# Spartan3_TestBoard_2.net
KiCad netlist of a schematic drawn in Altium Designer
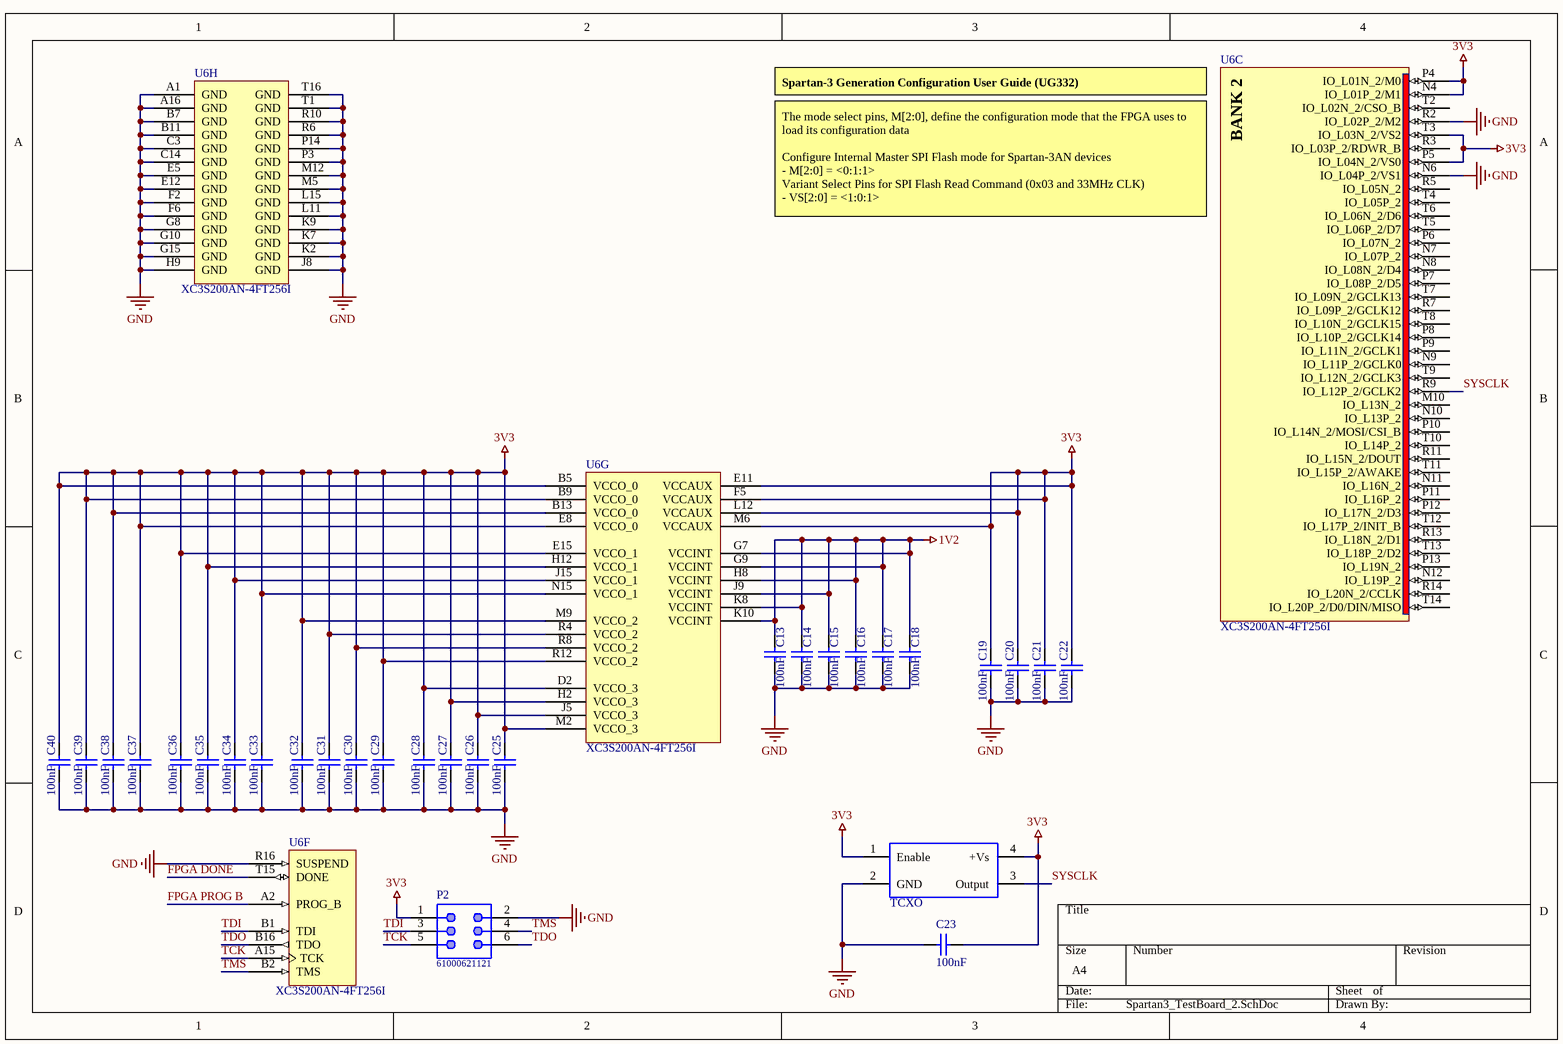
[diagram p0: Spartan3_TestBoard_2.SchDoc]

(export (version "E")
  (design (tool "Eeschema 10.0.6"))
  (components
    (comp (ref "C13")
      (value "100nF")
      (footprint "WCAP-CSGP_0402")
      (description "WCAP-CSGP General Purpose Ceramic Capacitors, size 0402, 100nF, +/-10%, 10VDC")
      (fields (field (name "PART NUMBER") "885012205018") (field (name "PUBLISHER") "Wurth Elektronik"))
      (libsource (lib "Altium_WCAP-CSGP (rev19a)") (part "885012205018"))
    )
    (comp (ref "C14")
      (value "100nF")
      (footprint "WCAP-CSGP_0402")
      (description "WCAP-CSGP General Purpose Ceramic Capacitors, size 0402, 100nF, +/-10%, 10VDC")
      (fields (field (name "PART NUMBER") "885012205018") (field (name "PUBLISHER") "Wurth Elektronik"))
      (libsource (lib "Altium_WCAP-CSGP (rev19a)") (part "885012205018"))
    )
    (comp (ref "C15")
      (value "100nF")
      (footprint "WCAP-CSGP_0402")
      (description "WCAP-CSGP General Purpose Ceramic Capacitors, size 0402, 100nF, +/-10%, 10VDC")
      (fields (field (name "PART NUMBER") "885012205018") (field (name "PUBLISHER") "Wurth Elektronik"))
      (libsource (lib "Altium_WCAP-CSGP (rev19a)") (part "885012205018"))
    )
    (comp (ref "C16")
      (value "100nF")
      (footprint "WCAP-CSGP_0402")
      (description "WCAP-CSGP General Purpose Ceramic Capacitors, size 0402, 100nF, +/-10%, 10VDC")
      (fields (field (name "PART NUMBER") "885012205018") (field (name "PUBLISHER") "Wurth Elektronik"))
      (libsource (lib "Altium_WCAP-CSGP (rev19a)") (part "885012205018"))
    )
    (comp (ref "C17")
      (value "100nF")
      (footprint "WCAP-CSGP_0402")
      (description "WCAP-CSGP General Purpose Ceramic Capacitors, size 0402, 100nF, +/-10%, 10VDC")
      (fields (field (name "PART NUMBER") "885012205018") (field (name "PUBLISHER") "Wurth Elektronik"))
      (libsource (lib "Altium_WCAP-CSGP (rev19a)") (part "885012205018"))
    )
    (comp (ref "C18")
      (value "100nF")
      (footprint "WCAP-CSGP_0402")
      (description "WCAP-CSGP General Purpose Ceramic Capacitors, size 0402, 100nF, +/-10%, 10VDC")
      (fields (field (name "PART NUMBER") "885012205018") (field (name "PUBLISHER") "Wurth Elektronik"))
      (libsource (lib "Altium_WCAP-CSGP (rev19a)") (part "885012205018"))
    )
    (comp (ref "C19")
      (value "100nF")
      (footprint "WCAP-CSGP_0402")
      (description "WCAP-CSGP General Purpose Ceramic Capacitors, size 0402, 100nF, +/-10%, 10VDC")
      (fields (field (name "PART NUMBER") "885012205018") (field (name "PUBLISHER") "Wurth Elektronik"))
      (libsource (lib "Altium_WCAP-CSGP (rev19a)") (part "885012205018"))
    )
    (comp (ref "C20")
      (value "100nF")
      (footprint "WCAP-CSGP_0402")
      (description "WCAP-CSGP General Purpose Ceramic Capacitors, size 0402, 100nF, +/-10%, 10VDC")
      (fields (field (name "PART NUMBER") "885012205018") (field (name "PUBLISHER") "Wurth Elektronik"))
      (libsource (lib "Altium_WCAP-CSGP (rev19a)") (part "885012205018"))
    )
    (comp (ref "C21")
      (value "100nF")
      (footprint "WCAP-CSGP_0402")
      (description "WCAP-CSGP General Purpose Ceramic Capacitors, size 0402, 100nF, +/-10%, 10VDC")
      (fields (field (name "PART NUMBER") "885012205018") (field (name "PUBLISHER") "Wurth Elektronik"))
      (libsource (lib "Altium_WCAP-CSGP (rev19a)") (part "885012205018"))
    )
    (comp (ref "C22")
      (value "100nF")
      (footprint "WCAP-CSGP_0402")
      (description "WCAP-CSGP General Purpose Ceramic Capacitors, size 0402, 100nF, +/-10%, 10VDC")
      (fields (field (name "PART NUMBER") "885012205018") (field (name "PUBLISHER") "Wurth Elektronik"))
      (libsource (lib "Altium_WCAP-CSGP (rev19a)") (part "885012205018"))
    )
    (comp (ref "C23")
      (value "100nF")
      (footprint "WCAP-CSGP_0402")
      (description "WCAP-CSGP General Purpose Ceramic Capacitors, size 0402, 100nF, +/-10%, 10VDC")
      (fields (field (name "PART NUMBER") "885012205018") (field (name "PUBLISHER") "Wurth Elektronik"))
      (libsource (lib "Altium_WCAP-CSGP (rev19a)") (part "885012205018"))
    )
    (comp (ref "C25")
      (value "100nF")
      (footprint "WCAP-CSGP_0402")
      (description "WCAP-CSGP General Purpose Ceramic Capacitors, size 0402, 100nF, +/-10%, 10VDC")
      (fields (field (name "PART NUMBER") "885012205018") (field (name "PUBLISHER") "Wurth Elektronik"))
      (libsource (lib "Altium_WCAP-CSGP (rev19a)") (part "885012205018"))
    )
    (comp (ref "C26")
      (value "100nF")
      (footprint "WCAP-CSGP_0402")
      (description "WCAP-CSGP General Purpose Ceramic Capacitors, size 0402, 100nF, +/-10%, 10VDC")
      (fields (field (name "PART NUMBER") "885012205018") (field (name "PUBLISHER") "Wurth Elektronik"))
      (libsource (lib "Altium_WCAP-CSGP (rev19a)") (part "885012205018"))
    )
    (comp (ref "C27")
      (value "100nF")
      (footprint "WCAP-CSGP_0402")
      (description "WCAP-CSGP General Purpose Ceramic Capacitors, size 0402, 100nF, +/-10%, 10VDC")
      (fields (field (name "PART NUMBER") "885012205018") (field (name "PUBLISHER") "Wurth Elektronik"))
      (libsource (lib "Altium_WCAP-CSGP (rev19a)") (part "885012205018"))
    )
    (comp (ref "C28")
      (value "100nF")
      (footprint "WCAP-CSGP_0402")
      (description "WCAP-CSGP General Purpose Ceramic Capacitors, size 0402, 100nF, +/-10%, 10VDC")
      (fields (field (name "PART NUMBER") "885012205018") (field (name "PUBLISHER") "Wurth Elektronik"))
      (libsource (lib "Altium_WCAP-CSGP (rev19a)") (part "885012205018"))
    )
    (comp (ref "C29")
      (value "100nF")
      (footprint "WCAP-CSGP_0402")
      (description "WCAP-CSGP General Purpose Ceramic Capacitors, size 0402, 100nF, +/-10%, 10VDC")
      (fields (field (name "PART NUMBER") "885012205018") (field (name "PUBLISHER") "Wurth Elektronik"))
      (libsource (lib "Altium_WCAP-CSGP (rev19a)") (part "885012205018"))
    )
    (comp (ref "C30")
      (value "100nF")
      (footprint "WCAP-CSGP_0402")
      (description "WCAP-CSGP General Purpose Ceramic Capacitors, size 0402, 100nF, +/-10%, 10VDC")
      (fields (field (name "PART NUMBER") "885012205018") (field (name "PUBLISHER") "Wurth Elektronik"))
      (libsource (lib "Altium_WCAP-CSGP (rev19a)") (part "885012205018"))
    )
    (comp (ref "C31")
      (value "100nF")
      (footprint "WCAP-CSGP_0402")
      (description "WCAP-CSGP General Purpose Ceramic Capacitors, size 0402, 100nF, +/-10%, 10VDC")
      (fields (field (name "PART NUMBER") "885012205018") (field (name "PUBLISHER") "Wurth Elektronik"))
      (libsource (lib "Altium_WCAP-CSGP (rev19a)") (part "885012205018"))
    )
    (comp (ref "C32")
      (value "100nF")
      (footprint "WCAP-CSGP_0402")
      (description "WCAP-CSGP General Purpose Ceramic Capacitors, size 0402, 100nF, +/-10%, 10VDC")
      (fields (field (name "PART NUMBER") "885012205018") (field (name "PUBLISHER") "Wurth Elektronik"))
      (libsource (lib "Altium_WCAP-CSGP (rev19a)") (part "885012205018"))
    )
    (comp (ref "C33")
      (value "100nF")
      (footprint "WCAP-CSGP_0402")
      (description "WCAP-CSGP General Purpose Ceramic Capacitors, size 0402, 100nF, +/-10%, 10VDC")
      (fields (field (name "PART NUMBER") "885012205018") (field (name "PUBLISHER") "Wurth Elektronik"))
      (libsource (lib "Altium_WCAP-CSGP (rev19a)") (part "885012205018"))
    )
    (comp (ref "C34")
      (value "100nF")
      (footprint "WCAP-CSGP_0402")
      (description "WCAP-CSGP General Purpose Ceramic Capacitors, size 0402, 100nF, +/-10%, 10VDC")
      (fields (field (name "PART NUMBER") "885012205018") (field (name "PUBLISHER") "Wurth Elektronik"))
      (libsource (lib "Altium_WCAP-CSGP (rev19a)") (part "885012205018"))
    )
    (comp (ref "C35")
      (value "100nF")
      (footprint "WCAP-CSGP_0402")
      (description "WCAP-CSGP General Purpose Ceramic Capacitors, size 0402, 100nF, +/-10%, 10VDC")
      (fields (field (name "PART NUMBER") "885012205018") (field (name "PUBLISHER") "Wurth Elektronik"))
      (libsource (lib "Altium_WCAP-CSGP (rev19a)") (part "885012205018"))
    )
    (comp (ref "C36")
      (value "100nF")
      (footprint "WCAP-CSGP_0402")
      (description "WCAP-CSGP General Purpose Ceramic Capacitors, size 0402, 100nF, +/-10%, 10VDC")
      (fields (field (name "PART NUMBER") "885012205018") (field (name "PUBLISHER") "Wurth Elektronik"))
      (libsource (lib "Altium_WCAP-CSGP (rev19a)") (part "885012205018"))
    )
    (comp (ref "C37")
      (value "100nF")
      (footprint "WCAP-CSGP_0402")
      (description "WCAP-CSGP General Purpose Ceramic Capacitors, size 0402, 100nF, +/-10%, 10VDC")
      (fields (field (name "PART NUMBER") "885012205018") (field (name "PUBLISHER") "Wurth Elektronik"))
      (libsource (lib "Altium_WCAP-CSGP (rev19a)") (part "885012205018"))
    )
    (comp (ref "C38")
      (value "100nF")
      (footprint "WCAP-CSGP_0402")
      (description "WCAP-CSGP General Purpose Ceramic Capacitors, size 0402, 100nF, +/-10%, 10VDC")
      (fields (field (name "PART NUMBER") "885012205018") (field (name "PUBLISHER") "Wurth Elektronik"))
      (libsource (lib "Altium_WCAP-CSGP (rev19a)") (part "885012205018"))
    )
    (comp (ref "C39")
      (value "100nF")
      (footprint "WCAP-CSGP_0402")
      (description "WCAP-CSGP General Purpose Ceramic Capacitors, size 0402, 100nF, +/-10%, 10VDC")
      (fields (field (name "PART NUMBER") "885012205018") (field (name "PUBLISHER") "Wurth Elektronik"))
      (libsource (lib "Altium_WCAP-CSGP (rev19a)") (part "885012205018"))
    )
    (comp (ref "C40")
      (value "100nF")
      (footprint "WCAP-CSGP_0402")
      (description "WCAP-CSGP General Purpose Ceramic Capacitors, size 0402, 100nF, +/-10%, 10VDC")
      (fields (field (name "PART NUMBER") "885012205018") (field (name "PUBLISHER") "Wurth Elektronik"))
      (libsource (lib "Altium_WCAP-CSGP (rev19a)") (part "885012205018"))
    )
    (comp (ref "P2")
      (value "61000621121")
      (footprint "61000621121")
      (description "WR-PHD Pin Header, SMT, pitch 2.54mm, Dual Row, Vertical, 6p")
      (fields (field (name "MANUFACTURER") "Wurth Elektronik"))
      (libsource (lib "Altium_WR-PHD (rev20a)") (part "61000621121"))
    )
    (comp (ref "TCXO")
      (value "12MHz, +/-50ppm, 3.3V")
      (footprint "WE-SPXO_CFPS-39")
      (description "WE-SPXO Simple Packaged Quartz Oscillator, size CFPS-39, 12MHz, +/-50ppm, 3.3V")
      (fields (field (name "PART NUMBER") "831025492") (field (name "PUBLISHER") "Wurth Elektronik"))
      (libsource (lib "Altium_WE-SPXO (rev19a)") (part "831025492"))
    )
    (comp (ref "U6")
      (value "XC3S200AN-4FT256I")
      (footprint "XC3S200AN-4FT256I")
      (libsource (lib "XC3S200AN-4FT256I") (part "XC3S200AN-4FT256I"))
    )
  )
  (nets
    (net (code "1") (name "/FPGA DONE") (class "Default")
      (node (ref "U6") (pin "T15") (pinfunction "DONE_T15") (pintype "bidirectional"))
    )
    (net (code "2") (name "/FPGA PROG B") (class "Default")
      (node (ref "U6") (pin "A2") (pinfunction "PROG_B_A2") (pintype "input"))
    )
    (net (code "3") (name "/SYSCLK") (class "Default")
      (node (ref "TCXO") (pin "3") (pinfunction "Output_3") (pintype "passive"))
      (node (ref "U6") (pin "R9") (pinfunction "IO_L12P_2/GCLK2_R9") (pintype "bidirectional"))
    )
    (net (code "4") (name "/TCK") (class "Default")
      (node (ref "P2") (pin "5") (pinfunction "5_5") (pintype "passive"))
      (node (ref "U6") (pin "A15") (pinfunction "TCK_A15") (pintype "input"))
    )
    (net (code "5") (name "/TDI") (class "Default")
      (node (ref "P2") (pin "3") (pinfunction "3_3") (pintype "passive"))
      (node (ref "U6") (pin "B1") (pinfunction "TDI_B1") (pintype "input"))
    )
    (net (code "6") (name "/TDO") (class "Default")
      (node (ref "P2") (pin "6") (pinfunction "6_6") (pintype "passive"))
      (node (ref "U6") (pin "B16") (pinfunction "TDO_B16") (pintype "output"))
    )
    (net (code "7") (name "/TMS") (class "Default")
      (node (ref "P2") (pin "4") (pinfunction "4_4") (pintype "passive"))
      (node (ref "U6") (pin "B2") (pinfunction "TMS_B2") (pintype "input"))
    )
    (net (code "8") (name "1V2") (class "Default")
      (node (ref "C13") (pin "1") (pinfunction "1_1") (pintype "passive"))
      (node (ref "C14") (pin "1") (pinfunction "1_1") (pintype "passive"))
      (node (ref "C15") (pin "1") (pinfunction "1_1") (pintype "passive"))
      (node (ref "C16") (pin "1") (pinfunction "1_1") (pintype "passive"))
      (node (ref "C17") (pin "1") (pinfunction "1_1") (pintype "passive"))
      (node (ref "C18") (pin "1") (pinfunction "1_1") (pintype "passive"))
      (node (ref "U6") (pin "G7") (pinfunction "VCCINT_G7") (pintype "power_in"))
      (node (ref "U6") (pin "G9") (pinfunction "VCCINT_G9") (pintype "power_in"))
      (node (ref "U6") (pin "H8") (pinfunction "VCCINT_H8") (pintype "power_in"))
      (node (ref "U6") (pin "J9") (pinfunction "VCCINT_J9") (pintype "power_in"))
      (node (ref "U6") (pin "K10") (pinfunction "VCCINT_K10") (pintype "power_in"))
      (node (ref "U6") (pin "K8") (pinfunction "VCCINT_K8") (pintype "power_in"))
    )
    (net (code "9") (name "3V3") (class "Default")
      (node (ref "C19") (pin "2") (pinfunction "2_2") (pintype "passive"))
      (node (ref "C20") (pin "2") (pinfunction "2_2") (pintype "passive"))
      (node (ref "C21") (pin "2") (pinfunction "2_2") (pintype "passive"))
      (node (ref "C22") (pin "2") (pinfunction "2_2") (pintype "passive"))
      (node (ref "C23") (pin "1") (pinfunction "1_1") (pintype "passive"))
      (node (ref "C25") (pin "2") (pinfunction "2_2") (pintype "passive"))
      (node (ref "C26") (pin "2") (pinfunction "2_2") (pintype "passive"))
      (node (ref "C27") (pin "2") (pinfunction "2_2") (pintype "passive"))
      (node (ref "C28") (pin "2") (pinfunction "2_2") (pintype "passive"))
      (node (ref "C29") (pin "2") (pinfunction "2_2") (pintype "passive"))
      (node (ref "C30") (pin "2") (pinfunction "2_2") (pintype "passive"))
      (node (ref "C31") (pin "2") (pinfunction "2_2") (pintype "passive"))
      (node (ref "C32") (pin "2") (pinfunction "2_2") (pintype "passive"))
      (node (ref "C33") (pin "2") (pinfunction "2_2") (pintype "passive"))
      (node (ref "C34") (pin "2") (pinfunction "2_2") (pintype "passive"))
      (node (ref "C35") (pin "2") (pinfunction "2_2") (pintype "passive"))
      (node (ref "C36") (pin "2") (pinfunction "2_2") (pintype "passive"))
      (node (ref "C37") (pin "2") (pinfunction "2_2") (pintype "passive"))
      (node (ref "C38") (pin "2") (pinfunction "2_2") (pintype "passive"))
      (node (ref "C39") (pin "2") (pinfunction "2_2") (pintype "passive"))
      (node (ref "C40") (pin "2") (pinfunction "2_2") (pintype "passive"))
      (node (ref "P2") (pin "1") (pinfunction "1_1") (pintype "passive"))
      (node (ref "TCXO") (pin "1") (pinfunction "Enable_1") (pintype "passive"))
      (node (ref "TCXO") (pin "4") (pinfunction "+Vs_4") (pintype "passive"))
      (node (ref "U6") (pin "B13") (pinfunction "VCCO_0_B13") (pintype "power_in"))
      (node (ref "U6") (pin "B5") (pinfunction "VCCO_0_B5") (pintype "power_in"))
      (node (ref "U6") (pin "B9") (pinfunction "VCCO_0_B9") (pintype "power_in"))
      (node (ref "U6") (pin "D2") (pinfunction "VCCO_3_D2") (pintype "power_in"))
      (node (ref "U6") (pin "E11") (pinfunction "VCCAUX_E11") (pintype "power_in"))
      (node (ref "U6") (pin "E15") (pinfunction "VCCO_1_E15") (pintype "power_in"))
      (node (ref "U6") (pin "E8") (pinfunction "VCCO_0_E8") (pintype "power_in"))
      (node (ref "U6") (pin "F5") (pinfunction "VCCAUX_F5") (pintype "power_in"))
      (node (ref "U6") (pin "H12") (pinfunction "VCCO_1_H12") (pintype "power_in"))
      (node (ref "U6") (pin "H2") (pinfunction "VCCO_3_H2") (pintype "power_in"))
      (node (ref "U6") (pin "J15") (pinfunction "VCCO_1_J15") (pintype "power_in"))
      (node (ref "U6") (pin "J5") (pinfunction "VCCO_3_J5") (pintype "power_in"))
      (node (ref "U6") (pin "L12") (pinfunction "VCCAUX_L12") (pintype "power_in"))
      (node (ref "U6") (pin "M2") (pinfunction "VCCO_3_M2") (pintype "power_in"))
      (node (ref "U6") (pin "M6") (pinfunction "VCCAUX_M6") (pintype "power_in"))
      (node (ref "U6") (pin "M9") (pinfunction "VCCO_2_M9") (pintype "power_in"))
      (node (ref "U6") (pin "N15") (pinfunction "VCCO_1_N15") (pintype "power_in"))
      (node (ref "U6") (pin "N4") (pinfunction "IO_L01P_2/M1_N4") (pintype "bidirectional"))
      (node (ref "U6") (pin "P4") (pinfunction "IO_L01N_2/M0_P4") (pintype "bidirectional"))
      (node (ref "U6") (pin "P5") (pinfunction "IO_L04N_2/VS0_P5") (pintype "bidirectional"))
      (node (ref "U6") (pin "R12") (pinfunction "VCCO_2_R12") (pintype "power_in"))
      (node (ref "U6") (pin "R4") (pinfunction "VCCO_2_R4") (pintype "power_in"))
      (node (ref "U6") (pin "R8") (pinfunction "VCCO_2_R8") (pintype "power_in"))
      (node (ref "U6") (pin "T3") (pinfunction "IO_L03N_2/VS2_T3") (pintype "bidirectional"))
    )
    (net (code "10") (name "GND") (class "Default")
      (node (ref "C13") (pin "2") (pinfunction "2_2") (pintype "passive"))
      (node (ref "C14") (pin "2") (pinfunction "2_2") (pintype "passive"))
      (node (ref "C15") (pin "2") (pinfunction "2_2") (pintype "passive"))
      (node (ref "C16") (pin "2") (pinfunction "2_2") (pintype "passive"))
      (node (ref "C17") (pin "2") (pinfunction "2_2") (pintype "passive"))
      (node (ref "C18") (pin "2") (pinfunction "2_2") (pintype "passive"))
      (node (ref "C19") (pin "1") (pinfunction "1_1") (pintype "passive"))
      (node (ref "C20") (pin "1") (pinfunction "1_1") (pintype "passive"))
      (node (ref "C21") (pin "1") (pinfunction "1_1") (pintype "passive"))
      (node (ref "C22") (pin "1") (pinfunction "1_1") (pintype "passive"))
      (node (ref "C23") (pin "2") (pinfunction "2_2") (pintype "passive"))
      (node (ref "C25") (pin "1") (pinfunction "1_1") (pintype "passive"))
      (node (ref "C26") (pin "1") (pinfunction "1_1") (pintype "passive"))
      (node (ref "C27") (pin "1") (pinfunction "1_1") (pintype "passive"))
      (node (ref "C28") (pin "1") (pinfunction "1_1") (pintype "passive"))
      (node (ref "C29") (pin "1") (pinfunction "1_1") (pintype "passive"))
      (node (ref "C30") (pin "1") (pinfunction "1_1") (pintype "passive"))
      (node (ref "C31") (pin "1") (pinfunction "1_1") (pintype "passive"))
      (node (ref "C32") (pin "1") (pinfunction "1_1") (pintype "passive"))
      (node (ref "C33") (pin "1") (pinfunction "1_1") (pintype "passive"))
      (node (ref "C34") (pin "1") (pinfunction "1_1") (pintype "passive"))
      (node (ref "C35") (pin "1") (pinfunction "1_1") (pintype "passive"))
      (node (ref "C36") (pin "1") (pinfunction "1_1") (pintype "passive"))
      (node (ref "C37") (pin "1") (pinfunction "1_1") (pintype "passive"))
      (node (ref "C38") (pin "1") (pinfunction "1_1") (pintype "passive"))
      (node (ref "C39") (pin "1") (pinfunction "1_1") (pintype "passive"))
      (node (ref "C40") (pin "1") (pinfunction "1_1") (pintype "passive"))
      (node (ref "P2") (pin "2") (pinfunction "2_2") (pintype "passive"))
      (node (ref "TCXO") (pin "2") (pinfunction "GND_2") (pintype "passive"))
      (node (ref "U6") (pin "A1") (pinfunction "GND_A1") (pintype "power_in"))
      (node (ref "U6") (pin "A16") (pinfunction "GND_A16") (pintype "power_in"))
      (node (ref "U6") (pin "B11") (pinfunction "GND_B11") (pintype "power_in"))
      (node (ref "U6") (pin "B7") (pinfunction "GND_B7") (pintype "power_in"))
      (node (ref "U6") (pin "C14") (pinfunction "GND_C14") (pintype "power_in"))
      (node (ref "U6") (pin "C3") (pinfunction "GND_C3") (pintype "power_in"))
      (node (ref "U6") (pin "E12") (pinfunction "GND_E12") (pintype "power_in"))
      (node (ref "U6") (pin "E5") (pinfunction "GND_E5") (pintype "power_in"))
      (node (ref "U6") (pin "F2") (pinfunction "GND_F2") (pintype "power_in"))
      (node (ref "U6") (pin "F6") (pinfunction "GND_F6") (pintype "power_in"))
      (node (ref "U6") (pin "G10") (pinfunction "GND_G10") (pintype "power_in"))
      (node (ref "U6") (pin "G15") (pinfunction "GND_G15") (pintype "power_in"))
      (node (ref "U6") (pin "G8") (pinfunction "GND_G8") (pintype "power_in"))
      (node (ref "U6") (pin "H9") (pinfunction "GND_H9") (pintype "power_in"))
      (node (ref "U6") (pin "J8") (pinfunction "GND_J8") (pintype "power_in"))
      (node (ref "U6") (pin "K2") (pinfunction "GND_K2") (pintype "power_in"))
      (node (ref "U6") (pin "K7") (pinfunction "GND_K7") (pintype "power_in"))
      (node (ref "U6") (pin "K9") (pinfunction "GND_K9") (pintype "power_in"))
      (node (ref "U6") (pin "L11") (pinfunction "GND_L11") (pintype "power_in"))
      (node (ref "U6") (pin "L15") (pinfunction "GND_L15") (pintype "power_in"))
      (node (ref "U6") (pin "M12") (pinfunction "GND_M12") (pintype "power_in"))
      (node (ref "U6") (pin "M5") (pinfunction "GND_M5") (pintype "power_in"))
      (node (ref "U6") (pin "N6") (pinfunction "IO_L04P_2/VS1_N6") (pintype "bidirectional"))
      (node (ref "U6") (pin "P14") (pinfunction "GND_P14") (pintype "power_in"))
      (node (ref "U6") (pin "P3") (pinfunction "GND_P3") (pintype "power_in"))
      (node (ref "U6") (pin "R10") (pinfunction "GND_R10") (pintype "power_in"))
      (node (ref "U6") (pin "R16") (pinfunction "SUSPEND_R16") (pintype "input"))
      (node (ref "U6") (pin "R2") (pinfunction "IO_L02P_2/M2_R2") (pintype "bidirectional"))
      (node (ref "U6") (pin "R6") (pinfunction "GND_R6") (pintype "power_in"))
      (node (ref "U6") (pin "T1") (pinfunction "GND_T1") (pintype "power_in"))
      (node (ref "U6") (pin "T16") (pinfunction "GND_T16") (pintype "power_in"))
    )
    (net (code "11") (name "unconnected-(U6C-IO_L02N_2{slash}CSO_B-PadT2)") (class "Default")
      (node (ref "U6") (pin "T2") (pinfunction "IO_L02N_2/CSO_B_T2") (pintype "bidirectional"))
    )
    (net (code "12") (name "unconnected-(U6C-IO_L03P_2{slash}RDWR_B-PadR3)") (class "Default")
      (node (ref "U6") (pin "R3") (pinfunction "IO_L03P_2/RDWR_B_R3") (pintype "bidirectional"))
    )
    (net (code "13") (name "unconnected-(U6C-IO_L05N_2-PadR5)") (class "Default")
      (node (ref "U6") (pin "R5") (pinfunction "IO_L05N_2_R5") (pintype "bidirectional"))
    )
    (net (code "14") (name "unconnected-(U6C-IO_L05P_2-PadT4)") (class "Default")
      (node (ref "U6") (pin "T4") (pinfunction "IO_L05P_2_T4") (pintype "bidirectional"))
    )
    (net (code "15") (name "unconnected-(U6C-IO_L06N_2{slash}D6-PadT6)") (class "Default")
      (node (ref "U6") (pin "T6") (pinfunction "IO_L06N_2/D6_T6") (pintype "bidirectional"))
    )
    (net (code "16") (name "unconnected-(U6C-IO_L06P_2{slash}D7-PadT5)") (class "Default")
      (node (ref "U6") (pin "T5") (pinfunction "IO_L06P_2/D7_T5") (pintype "bidirectional"))
    )
    (net (code "17") (name "unconnected-(U6C-IO_L07N_2-PadP6)") (class "Default")
      (node (ref "U6") (pin "P6") (pinfunction "IO_L07N_2_P6") (pintype "bidirectional"))
    )
    (net (code "18") (name "unconnected-(U6C-IO_L07P_2-PadN7)") (class "Default")
      (node (ref "U6") (pin "N7") (pinfunction "IO_L07P_2_N7") (pintype "bidirectional"))
    )
    (net (code "19") (name "unconnected-(U6C-IO_L08N_2{slash}D4-PadN8)") (class "Default")
      (node (ref "U6") (pin "N8") (pinfunction "IO_L08N_2/D4_N8") (pintype "bidirectional"))
    )
    (net (code "20") (name "unconnected-(U6C-IO_L08P_2{slash}D5-PadP7)") (class "Default")
      (node (ref "U6") (pin "P7") (pinfunction "IO_L08P_2/D5_P7") (pintype "bidirectional"))
    )
    (net (code "21") (name "unconnected-(U6C-IO_L09N_2{slash}GCLK13-PadT7)") (class "Default")
      (node (ref "U6") (pin "T7") (pinfunction "IO_L09N_2/GCLK13_T7") (pintype "bidirectional"))
    )
    (net (code "22") (name "unconnected-(U6C-IO_L09P_2{slash}GCLK12-PadR7)") (class "Default")
      (node (ref "U6") (pin "R7") (pinfunction "IO_L09P_2/GCLK12_R7") (pintype "bidirectional"))
    )
    (net (code "23") (name "unconnected-(U6C-IO_L10N_2{slash}GCLK15-PadT8)") (class "Default")
      (node (ref "U6") (pin "T8") (pinfunction "IO_L10N_2/GCLK15_T8") (pintype "bidirectional"))
    )
    (net (code "24") (name "unconnected-(U6C-IO_L10P_2{slash}GCLK14-PadP8)") (class "Default")
      (node (ref "U6") (pin "P8") (pinfunction "IO_L10P_2/GCLK14_P8") (pintype "bidirectional"))
    )
    (net (code "25") (name "unconnected-(U6C-IO_L11N_2{slash}GCLK1-PadP9)") (class "Default")
      (node (ref "U6") (pin "P9") (pinfunction "IO_L11N_2/GCLK1_P9") (pintype "bidirectional"))
    )
    (net (code "26") (name "unconnected-(U6C-IO_L11P_2{slash}GCLK0-PadN9)") (class "Default")
      (node (ref "U6") (pin "N9") (pinfunction "IO_L11P_2/GCLK0_N9") (pintype "bidirectional"))
    )
    (net (code "27") (name "unconnected-(U6C-IO_L12N_2{slash}GCLK3-PadT9)") (class "Default")
      (node (ref "U6") (pin "T9") (pinfunction "IO_L12N_2/GCLK3_T9") (pintype "bidirectional"))
    )
    (net (code "28") (name "unconnected-(U6C-IO_L13N_2-PadM10)") (class "Default")
      (node (ref "U6") (pin "M10") (pinfunction "IO_L13N_2_M10") (pintype "bidirectional"))
    )
    (net (code "29") (name "unconnected-(U6C-IO_L13P_2-PadN10)") (class "Default")
      (node (ref "U6") (pin "N10") (pinfunction "IO_L13P_2_N10") (pintype "bidirectional"))
    )
    (net (code "30") (name "unconnected-(U6C-IO_L14N_2{slash}MOSI{slash}CSI_B-PadP10)") (class "Default")
      (node (ref "U6") (pin "P10") (pinfunction "IO_L14N_2/MOSI/CSI_B_P10") (pintype "bidirectional"))
    )
    (net (code "31") (name "unconnected-(U6C-IO_L14P_2-PadT10)") (class "Default")
      (node (ref "U6") (pin "T10") (pinfunction "IO_L14P_2_T10") (pintype "bidirectional"))
    )
    (net (code "32") (name "unconnected-(U6C-IO_L15N_2{slash}DOUT-PadR11)") (class "Default")
      (node (ref "U6") (pin "R11") (pinfunction "IO_L15N_2/DOUT_R11") (pintype "bidirectional"))
    )
    (net (code "33") (name "unconnected-(U6C-IO_L15P_2{slash}AWAKE-PadT11)") (class "Default")
      (node (ref "U6") (pin "T11") (pinfunction "IO_L15P_2/AWAKE_T11") (pintype "bidirectional"))
    )
    (net (code "34") (name "unconnected-(U6C-IO_L16N_2-PadN11)") (class "Default")
      (node (ref "U6") (pin "N11") (pinfunction "IO_L16N_2_N11") (pintype "bidirectional"))
    )
    (net (code "35") (name "unconnected-(U6C-IO_L16P_2-PadP11)") (class "Default")
      (node (ref "U6") (pin "P11") (pinfunction "IO_L16P_2_P11") (pintype "bidirectional"))
    )
    (net (code "36") (name "unconnected-(U6C-IO_L17N_2{slash}D3-PadP12)") (class "Default")
      (node (ref "U6") (pin "P12") (pinfunction "IO_L17N_2/D3_P12") (pintype "bidirectional"))
    )
    (net (code "37") (name "unconnected-(U6C-IO_L17P_2{slash}INIT_B-PadT12)") (class "Default")
      (node (ref "U6") (pin "T12") (pinfunction "IO_L17P_2/INIT_B_T12") (pintype "bidirectional"))
    )
    (net (code "38") (name "unconnected-(U6C-IO_L18N_2{slash}D1-PadR13)") (class "Default")
      (node (ref "U6") (pin "R13") (pinfunction "IO_L18N_2/D1_R13") (pintype "bidirectional"))
    )
    (net (code "39") (name "unconnected-(U6C-IO_L18P_2{slash}D2-PadT13)") (class "Default")
      (node (ref "U6") (pin "T13") (pinfunction "IO_L18P_2/D2_T13") (pintype "bidirectional"))
    )
    (net (code "40") (name "unconnected-(U6C-IO_L19N_2-PadP13)") (class "Default")
      (node (ref "U6") (pin "P13") (pinfunction "IO_L19N_2_P13") (pintype "bidirectional"))
    )
    (net (code "41") (name "unconnected-(U6C-IO_L19P_2-PadN12)") (class "Default")
      (node (ref "U6") (pin "N12") (pinfunction "IO_L19P_2_N12") (pintype "bidirectional"))
    )
    (net (code "42") (name "unconnected-(U6C-IO_L20N_2{slash}CCLK-PadR14)") (class "Default")
      (node (ref "U6") (pin "R14") (pinfunction "IO_L20N_2/CCLK_R14") (pintype "bidirectional"))
    )
    (net (code "43") (name "unconnected-(U6C-IO_L20P_2{slash}D0{slash}DIN{slash}MISO-PadT14)") (class "Default")
      (node (ref "U6") (pin "T14") (pinfunction "IO_L20P_2/D0/DIN/MISO_T14") (pintype "bidirectional"))
    )
  )
)
